# AccelPCB.net
KiCad netlist of a schematic drawn in Altium Designer
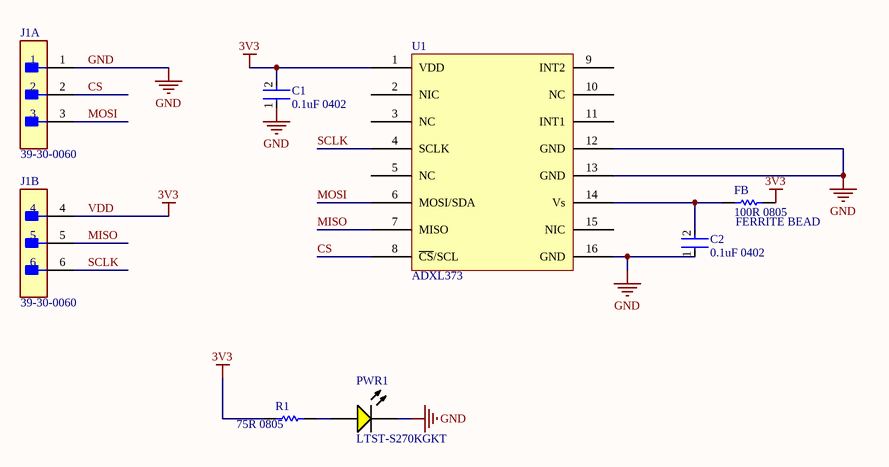
[diagram p0: AccelPCB.SchDoc]

(export (version "E")
  (design (tool "Eeschema 10.0.6"))
  (components
    (comp (ref "C1")
      (value "0.1uF 0402")
      (footprint "FP-GRM15-MFG")
      (description "CAP CER 0.1UF 16V X7R 0402")
      (fields (field (name "MANUFACTURER PART NUMBER") "GRM155R71C104KA88D") (field (name "TOLERANCE") "10%"))
      (libsource (lib "Altium Content Vault") (part "236180d848d6139a670b325ea6854c9"))
    )
    (comp (ref "C2")
      (value "0.1uF 0402")
      (footprint "FP-GRM15-MFG")
      (description "CAP CER 0.1UF 16V X7R 0402")
      (fields (field (name "MANUFACTURER PART NUMBER") "GRM155R71C104KA88D") (field (name "TOLERANCE") "10%"))
      (libsource (lib "Altium Content Vault") (part "236180d848d6139a670b325ea6854c9"))
    )
    (comp (ref "FB")
      (value "100R 0805")
      (footprint "RESC2013X50X30LL20T20")
      (fields (field (name "MANUFACTURER") "Vishay Dale") (field (name "PART NUMBER") "CRCW08050000Z0EA"))
      (libsource (lib "Altium Content Vault") (part "RES"))
    )
    (comp (ref "J1")
      (value "39-30-0060")
      (footprint "FP-39-30-0060-MFG")
      (description "CONN HEADER R/A 6POS 4.2MM")
      (libsource (lib "Altium Content Vault") (part "bb9cbdb24149a20ba329b4e86909569"))
    )
    (comp (ref "PWR1")
      (value "LTST-S270KGKT")
      (footprint "AVAG-HSMX-C190_V")
      (description "LED Uni-Color Yellow, 65 mW, 20 mA, -40 to 85 degC, 2-Pin SMD, RoHS, Tape and Reel")
      (fields (field (name "TOLERANCE") "1%"))
      (libsource (lib "Altium Content Vault") (part "LED-YELLOW-AK-2"))
    )
    (comp (ref "R1")
      (value "75R 0805")
      (footprint "RESC2013X50X30LL20T20")
      (fields (field (name "MANUFACTURER") "Vishay Dale") (field (name "PART NUMBER") "CRCW08050000Z0EA"))
      (libsource (lib "Altium Content Vault") (part "RES"))
    )
    (comp (ref "U1")
      (value "ADXL373")
      (footprint "FP-CC-16-3-MFG")
      (libsource (lib "ADXL373") (part "Component_1"))
    )
  )
  (nets
    (net (code "1") (name "/CS") (class "Default")
      (node (ref "J1") (pin "2") (pinfunction "2_2") (pintype "passive"))
      (node (ref "U1") (pin "8") (pinfunction "~{CS}/SCL_8") (pintype "passive"))
    )
    (net (code "2") (name "/MISO") (class "Default")
      (node (ref "J1") (pin "5") (pinfunction "5_5") (pintype "passive"))
      (node (ref "U1") (pin "7") (pinfunction "MISO_7") (pintype "passive"))
    )
    (net (code "3") (name "/MOSI") (class "Default")
      (node (ref "J1") (pin "3") (pinfunction "3_3") (pintype "passive"))
      (node (ref "U1") (pin "6") (pinfunction "MOSI/SDA_6") (pintype "passive"))
    )
    (net (code "4") (name "/SCLK") (class "Default")
      (node (ref "J1") (pin "6") (pinfunction "6_6") (pintype "passive"))
      (node (ref "U1") (pin "4") (pinfunction "SCLK_4") (pintype "passive"))
    )
    (net (code "5") (name "3V3") (class "Default")
      (node (ref "C1") (pin "2") (pinfunction "2_2") (pintype "passive"))
      (node (ref "FB") (pin "2") (pinfunction "2_2") (pintype "passive"))
      (node (ref "J1") (pin "4") (pinfunction "4_4") (pintype "passive"))
      (node (ref "R1") (pin "1") (pinfunction "1_1") (pintype "passive"))
      (node (ref "U1") (pin "1") (pinfunction "VDD_1") (pintype "passive"))
    )
    (net (code "6") (name "GND") (class "Default")
      (node (ref "C1") (pin "1") (pinfunction "1_1") (pintype "passive"))
      (node (ref "C2") (pin "1") (pinfunction "1_1") (pintype "passive"))
      (node (ref "J1") (pin "1") (pinfunction "1_1") (pintype "passive"))
      (node (ref "PWR1") (pin "2") (pinfunction "K_2") (pintype "passive"))
      (node (ref "U1") (pin "12") (pinfunction "GND_12") (pintype "passive"))
      (node (ref "U1") (pin "13") (pinfunction "GND_13") (pintype "passive"))
      (node (ref "U1") (pin "16") (pinfunction "GND_16") (pintype "passive"))
    )
    (net (code "7") (name "Net-(PWR1-A)") (class "Default")
      (node (ref "PWR1") (pin "1") (pinfunction "A_1") (pintype "passive"))
      (node (ref "R1") (pin "2") (pinfunction "2_2") (pintype "passive"))
    )
    (net (code "8") (name "Net-(U1-Vs)") (class "Default")
      (node (ref "C2") (pin "2") (pinfunction "2_2") (pintype "passive"))
      (node (ref "FB") (pin "1") (pinfunction "1_1") (pintype "passive"))
      (node (ref "U1") (pin "14") (pinfunction "Vs_14") (pintype "passive"))
    )
    (net (code "9") (name "unconnected-(U1-INT1-Pad11)") (class "Default")
      (node (ref "U1") (pin "11") (pinfunction "INT1_11") (pintype "passive"))
    )
    (net (code "10") (name "unconnected-(U1-INT2-Pad9)") (class "Default")
      (node (ref "U1") (pin "9") (pinfunction "INT2_9") (pintype "passive"))
    )
    (net (code "11") (name "unconnected-(U1-NC-Pad3)") (class "Default")
      (node (ref "U1") (pin "3") (pinfunction "NC_3") (pintype "passive"))
    )
    (net (code "12") (name "unconnected-(U1-NC-Pad5)") (class "Default")
      (node (ref "U1") (pin "5") (pinfunction "NC_5") (pintype "passive"))
    )
    (net (code "13") (name "unconnected-(U1-NC-Pad10)") (class "Default")
      (node (ref "U1") (pin "10") (pinfunction "NC_10") (pintype "passive"))
    )
    (net (code "14") (name "unconnected-(U1-NIC-Pad2)") (class "Default")
      (node (ref "U1") (pin "2") (pinfunction "NIC_2") (pintype "passive"))
    )
    (net (code "15") (name "unconnected-(U1-NIC-Pad15)") (class "Default")
      (node (ref "U1") (pin "15") (pinfunction "NIC_15") (pintype "passive"))
    )
  )
)
